# S284B.net
KiCad netlist of a schematic drawn in EAGLE
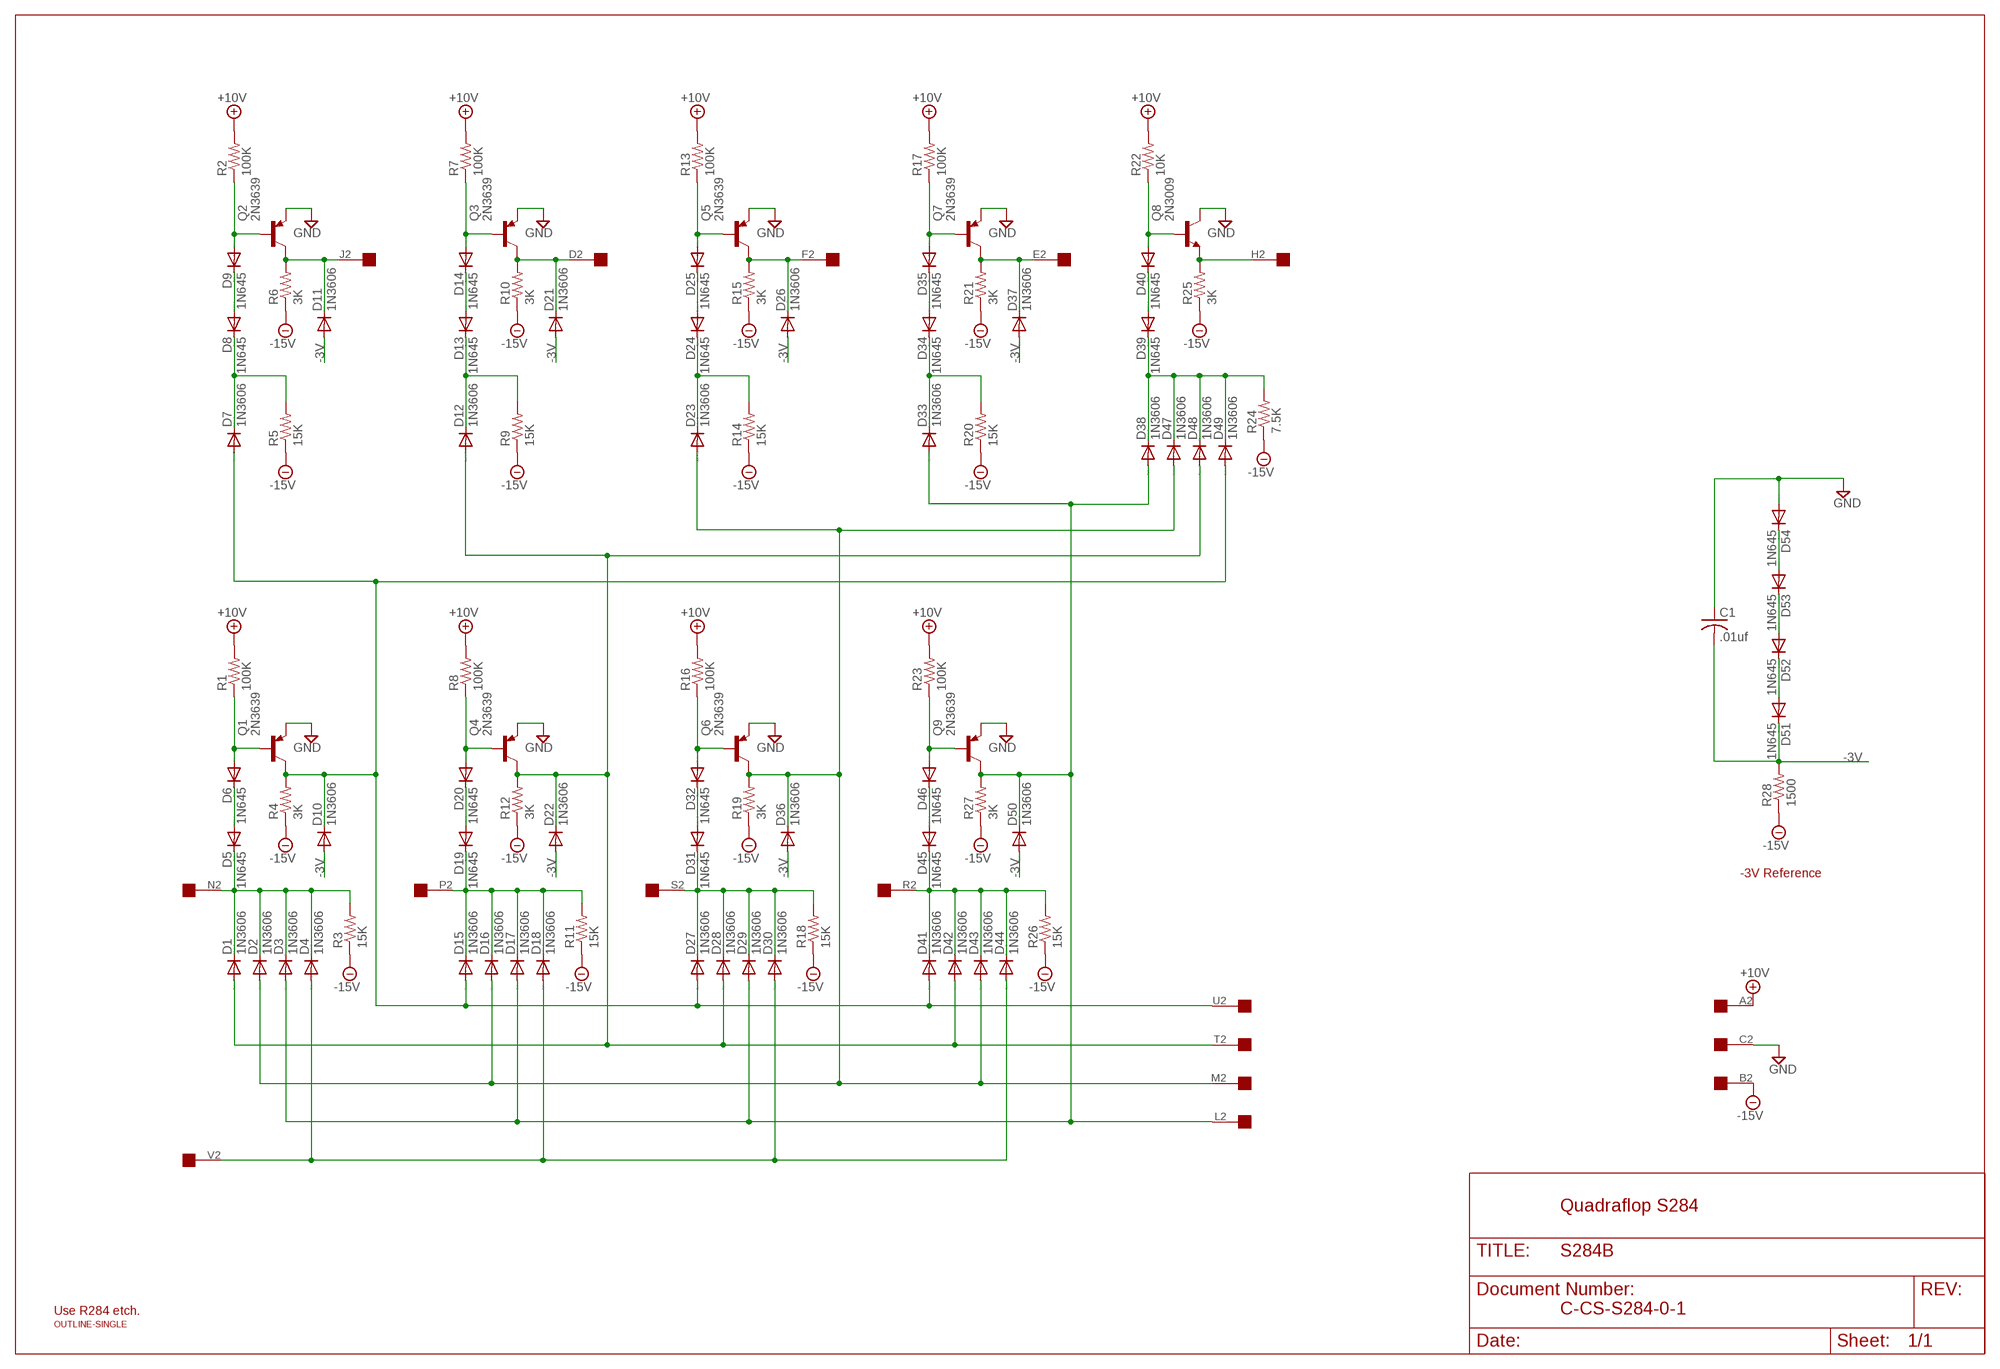
[diagram p0: schematic, sheet 1]

(export (version "E")
  (design (tool "Eeschema 10.0.6"))
  (components
    (comp (ref "C1")
      (value ".01uf")
      (footprint "eagle-import:C050-025X075")
      (libsource (lib "eagle-import") (part "C-US050-025X075"))
    )
    (comp (ref "D1")
      (value "1N3606")
      (footprint "eagle-import:DO35-10")
      (libsource (lib "eagle-import") (part "1N4148DO35-10"))
    )
    (comp (ref "D2")
      (value "1N3606")
      (footprint "eagle-import:DO35-10")
      (libsource (lib "eagle-import") (part "1N4148DO35-10"))
    )
    (comp (ref "D3")
      (value "1N3606")
      (footprint "eagle-import:DO35-10")
      (libsource (lib "eagle-import") (part "1N4148DO35-10"))
    )
    (comp (ref "D4")
      (value "1N3606")
      (footprint "eagle-import:DO35-10")
      (libsource (lib "eagle-import") (part "1N4148DO35-10"))
    )
    (comp (ref "D5")
      (value "1N645")
      (footprint "eagle-import:DO35-10")
      (libsource (lib "eagle-import") (part "1N4148DO35-10"))
    )
    (comp (ref "D6")
      (value "1N645")
      (footprint "eagle-import:DO35-10")
      (libsource (lib "eagle-import") (part "1N4148DO35-10"))
    )
    (comp (ref "D7")
      (value "1N3606")
      (footprint "eagle-import:DO35-10")
      (libsource (lib "eagle-import") (part "1N4148DO35-10"))
    )
    (comp (ref "D8")
      (value "1N645")
      (footprint "eagle-import:DO35-10")
      (libsource (lib "eagle-import") (part "1N4148DO35-10"))
    )
    (comp (ref "D9")
      (value "1N645")
      (footprint "eagle-import:DO35-10")
      (libsource (lib "eagle-import") (part "1N4148DO35-10"))
    )
    (comp (ref "D10")
      (value "1N3606")
      (footprint "eagle-import:DO35-10")
      (libsource (lib "eagle-import") (part "1N4148DO35-10"))
    )
    (comp (ref "D11")
      (value "1N3606")
      (footprint "eagle-import:DO35-10")
      (libsource (lib "eagle-import") (part "1N4148DO35-10"))
    )
    (comp (ref "D12")
      (value "1N3606")
      (footprint "eagle-import:DO35-10")
      (libsource (lib "eagle-import") (part "1N4148DO35-10"))
    )
    (comp (ref "D13")
      (value "1N645")
      (footprint "eagle-import:DO35-10")
      (libsource (lib "eagle-import") (part "1N4148DO35-10"))
    )
    (comp (ref "D14")
      (value "1N645")
      (footprint "eagle-import:DO35-10")
      (libsource (lib "eagle-import") (part "1N4148DO35-10"))
    )
    (comp (ref "D15")
      (value "1N3606")
      (footprint "eagle-import:DO35-10")
      (libsource (lib "eagle-import") (part "1N4148DO35-10"))
    )
    (comp (ref "D16")
      (value "1N3606")
      (footprint "eagle-import:DO35-10")
      (libsource (lib "eagle-import") (part "1N4148DO35-10"))
    )
    (comp (ref "D17")
      (value "1N3606")
      (footprint "eagle-import:DO35-10")
      (libsource (lib "eagle-import") (part "1N4148DO35-10"))
    )
    (comp (ref "D18")
      (value "1N3606")
      (footprint "eagle-import:DO35-10")
      (libsource (lib "eagle-import") (part "1N4148DO35-10"))
    )
    (comp (ref "D19")
      (value "1N645")
      (footprint "eagle-import:DO35-10")
      (libsource (lib "eagle-import") (part "1N4148DO35-10"))
    )
    (comp (ref "D20")
      (value "1N645")
      (footprint "eagle-import:DO35-10")
      (libsource (lib "eagle-import") (part "1N4148DO35-10"))
    )
    (comp (ref "D21")
      (value "1N3606")
      (footprint "eagle-import:DO35-10")
      (libsource (lib "eagle-import") (part "1N4148DO35-10"))
    )
    (comp (ref "D22")
      (value "1N3606")
      (footprint "eagle-import:DO35-10")
      (libsource (lib "eagle-import") (part "1N4148DO35-10"))
    )
    (comp (ref "D23")
      (value "1N3606")
      (footprint "eagle-import:DO35-10")
      (libsource (lib "eagle-import") (part "1N4148DO35-10"))
    )
    (comp (ref "D24")
      (value "1N645")
      (footprint "eagle-import:DO35-10")
      (libsource (lib "eagle-import") (part "1N4148DO35-10"))
    )
    (comp (ref "D25")
      (value "1N645")
      (footprint "eagle-import:DO35-10")
      (libsource (lib "eagle-import") (part "1N4148DO35-10"))
    )
    (comp (ref "D26")
      (value "1N3606")
      (footprint "eagle-import:DO35-10")
      (libsource (lib "eagle-import") (part "1N4148DO35-10"))
    )
    (comp (ref "D27")
      (value "1N3606")
      (footprint "eagle-import:DO35-10")
      (libsource (lib "eagle-import") (part "1N4148DO35-10"))
    )
    (comp (ref "D28")
      (value "1N3606")
      (footprint "eagle-import:DO35-10")
      (libsource (lib "eagle-import") (part "1N4148DO35-10"))
    )
    (comp (ref "D29")
      (value "1N3606")
      (footprint "eagle-import:DO35-10")
      (libsource (lib "eagle-import") (part "1N4148DO35-10"))
    )
    (comp (ref "D30")
      (value "1N3606")
      (footprint "eagle-import:DO35-10")
      (libsource (lib "eagle-import") (part "1N4148DO35-10"))
    )
    (comp (ref "D31")
      (value "1N645")
      (footprint "eagle-import:DO35-10")
      (libsource (lib "eagle-import") (part "1N4148DO35-10"))
    )
    (comp (ref "D32")
      (value "1N645")
      (footprint "eagle-import:DO35-10")
      (libsource (lib "eagle-import") (part "1N4148DO35-10"))
    )
    (comp (ref "D33")
      (value "1N3606")
      (footprint "eagle-import:DO35-10")
      (libsource (lib "eagle-import") (part "1N4148DO35-10"))
    )
    (comp (ref "D34")
      (value "1N645")
      (footprint "eagle-import:DO35-10")
      (libsource (lib "eagle-import") (part "1N4148DO35-10"))
    )
    (comp (ref "D35")
      (value "1N645")
      (footprint "eagle-import:DO35-10")
      (libsource (lib "eagle-import") (part "1N4148DO35-10"))
    )
    (comp (ref "D36")
      (value "1N3606")
      (footprint "eagle-import:DO35-10")
      (libsource (lib "eagle-import") (part "1N4148DO35-10"))
    )
    (comp (ref "D37")
      (value "1N3606")
      (footprint "eagle-import:DO35-10")
      (libsource (lib "eagle-import") (part "1N4148DO35-10"))
    )
    (comp (ref "D38")
      (value "1N3606")
      (footprint "eagle-import:DO35-10")
      (libsource (lib "eagle-import") (part "1N4148DO35-10"))
    )
    (comp (ref "D39")
      (value "1N645")
      (footprint "eagle-import:DO35-10")
      (libsource (lib "eagle-import") (part "1N4148DO35-10"))
    )
    (comp (ref "D40")
      (value "1N645")
      (footprint "eagle-import:DO35-10")
      (libsource (lib "eagle-import") (part "1N4148DO35-10"))
    )
    (comp (ref "D41")
      (value "1N3606")
      (footprint "eagle-import:DO35-10")
      (libsource (lib "eagle-import") (part "1N4148DO35-10"))
    )
    (comp (ref "D42")
      (value "1N3606")
      (footprint "eagle-import:DO35-10")
      (libsource (lib "eagle-import") (part "1N4148DO35-10"))
    )
    (comp (ref "D43")
      (value "1N3606")
      (footprint "eagle-import:DO35-10")
      (libsource (lib "eagle-import") (part "1N4148DO35-10"))
    )
    (comp (ref "D44")
      (value "1N3606")
      (footprint "eagle-import:DO35-10")
      (libsource (lib "eagle-import") (part "1N4148DO35-10"))
    )
    (comp (ref "D45")
      (value "1N645")
      (footprint "eagle-import:DO35-10")
      (libsource (lib "eagle-import") (part "1N4148DO35-10"))
    )
    (comp (ref "D46")
      (value "1N645")
      (footprint "eagle-import:DO35-10")
      (libsource (lib "eagle-import") (part "1N4148DO35-10"))
    )
    (comp (ref "D47")
      (value "1N3606")
      (footprint "eagle-import:DO35-10")
      (libsource (lib "eagle-import") (part "1N4148DO35-10"))
    )
    (comp (ref "D48")
      (value "1N3606")
      (footprint "eagle-import:DO35-10")
      (libsource (lib "eagle-import") (part "1N4148DO35-10"))
    )
    (comp (ref "D49")
      (value "1N3606")
      (footprint "eagle-import:DO35-10")
      (libsource (lib "eagle-import") (part "1N4148DO35-10"))
    )
    (comp (ref "D50")
      (value "1N3606")
      (footprint "eagle-import:DO35-10")
      (libsource (lib "eagle-import") (part "1N4148DO35-10"))
    )
    (comp (ref "D51")
      (value "1N645")
      (footprint "eagle-import:DO35-10")
      (libsource (lib "eagle-import") (part "1N4148DO35-10"))
    )
    (comp (ref "D52")
      (value "1N645")
      (footprint "eagle-import:DO35-10")
      (libsource (lib "eagle-import") (part "1N4148DO35-10"))
    )
    (comp (ref "D53")
      (value "1N645")
      (footprint "eagle-import:DO35-10")
      (libsource (lib "eagle-import") (part "1N4148DO35-10"))
    )
    (comp (ref "D54")
      (value "1N645")
      (footprint "eagle-import:DO35-10")
      (libsource (lib "eagle-import") (part "1N4148DO35-10"))
    )
    (comp (ref "Q1")
      (value "2N3639")
      (footprint "eagle-import:TO39")
      (libsource (lib "eagle-import") (part "2N3637"))
    )
    (comp (ref "Q2")
      (value "2N3639")
      (footprint "eagle-import:TO39")
      (libsource (lib "eagle-import") (part "2N3637"))
    )
    (comp (ref "Q3")
      (value "2N3639")
      (footprint "eagle-import:TO39")
      (libsource (lib "eagle-import") (part "2N3637"))
    )
    (comp (ref "Q4")
      (value "2N3639")
      (footprint "eagle-import:TO39")
      (libsource (lib "eagle-import") (part "2N3637"))
    )
    (comp (ref "Q5")
      (value "2N3639")
      (footprint "eagle-import:TO39")
      (libsource (lib "eagle-import") (part "2N3637"))
    )
    (comp (ref "Q6")
      (value "2N3639")
      (footprint "eagle-import:TO39")
      (libsource (lib "eagle-import") (part "2N3637"))
    )
    (comp (ref "Q7")
      (value "2N3639")
      (footprint "eagle-import:TO39")
      (libsource (lib "eagle-import") (part "2N3637"))
    )
    (comp (ref "Q8")
      (value "2N3009")
      (footprint "eagle-import:TO5")
      (libsource (lib "eagle-import") (part "2N2102"))
    )
    (comp (ref "Q9")
      (value "2N3639")
      (footprint "eagle-import:TO39")
      (libsource (lib "eagle-import") (part "2N3637"))
    )
    (comp (ref "R1")
      (value "100K")
      (footprint "eagle-import:0207_10")
      (libsource (lib "eagle-import") (part "R-US_0207/10"))
    )
    (comp (ref "R2")
      (value "100K")
      (footprint "eagle-import:0207_10")
      (libsource (lib "eagle-import") (part "R-US_0207/10"))
    )
    (comp (ref "R3")
      (value "15K")
      (footprint "eagle-import:0207_10")
      (libsource (lib "eagle-import") (part "R-US_0207/10"))
    )
    (comp (ref "R4")
      (value "3K")
      (footprint "eagle-import:0207_10")
      (libsource (lib "eagle-import") (part "R-US_0207/10"))
    )
    (comp (ref "R5")
      (value "15K")
      (footprint "eagle-import:0207_10")
      (libsource (lib "eagle-import") (part "R-US_0207/10"))
    )
    (comp (ref "R6")
      (value "3K")
      (footprint "eagle-import:0207_10")
      (libsource (lib "eagle-import") (part "R-US_0207/10"))
    )
    (comp (ref "R7")
      (value "100K")
      (footprint "eagle-import:0207_10")
      (libsource (lib "eagle-import") (part "R-US_0207/10"))
    )
    (comp (ref "R8")
      (value "100K")
      (footprint "eagle-import:0207_10")
      (libsource (lib "eagle-import") (part "R-US_0207/10"))
    )
    (comp (ref "R9")
      (value "15K")
      (footprint "eagle-import:0207_10")
      (libsource (lib "eagle-import") (part "R-US_0207/10"))
    )
    (comp (ref "R10")
      (value "3K")
      (footprint "eagle-import:0207_10")
      (libsource (lib "eagle-import") (part "R-US_0207/10"))
    )
    (comp (ref "R11")
      (value "15K")
      (footprint "eagle-import:0207_10")
      (libsource (lib "eagle-import") (part "R-US_0207/10"))
    )
    (comp (ref "R12")
      (value "3K")
      (footprint "eagle-import:0207_10")
      (libsource (lib "eagle-import") (part "R-US_0207/10"))
    )
    (comp (ref "R13")
      (value "100K")
      (footprint "eagle-import:0207_10")
      (libsource (lib "eagle-import") (part "R-US_0207/10"))
    )
    (comp (ref "R14")
      (value "15K")
      (footprint "eagle-import:0207_10")
      (libsource (lib "eagle-import") (part "R-US_0207/10"))
    )
    (comp (ref "R15")
      (value "3K")
      (footprint "eagle-import:0207_10")
      (libsource (lib "eagle-import") (part "R-US_0207/10"))
    )
    (comp (ref "R16")
      (value "100K")
      (footprint "eagle-import:0207_10")
      (libsource (lib "eagle-import") (part "R-US_0207/10"))
    )
    (comp (ref "R17")
      (value "100K")
      (footprint "eagle-import:0207_10")
      (libsource (lib "eagle-import") (part "R-US_0207/10"))
    )
    (comp (ref "R18")
      (value "15K")
      (footprint "eagle-import:0207_10")
      (libsource (lib "eagle-import") (part "R-US_0207/10"))
    )
    (comp (ref "R19")
      (value "3K")
      (footprint "eagle-import:0207_10")
      (libsource (lib "eagle-import") (part "R-US_0207/10"))
    )
    (comp (ref "R20")
      (value "15K")
      (footprint "eagle-import:0207_10")
      (libsource (lib "eagle-import") (part "R-US_0207/10"))
    )
    (comp (ref "R21")
      (value "3K")
      (footprint "eagle-import:0207_10")
      (libsource (lib "eagle-import") (part "R-US_0207/10"))
    )
    (comp (ref "R22")
      (value "10K")
      (footprint "eagle-import:0207_10")
      (libsource (lib "eagle-import") (part "R-US_0207/10"))
    )
    (comp (ref "R23")
      (value "100K")
      (footprint "eagle-import:0207_10")
      (libsource (lib "eagle-import") (part "R-US_0207/10"))
    )
    (comp (ref "R24")
      (value "7.5K")
      (footprint "eagle-import:0207_10")
      (libsource (lib "eagle-import") (part "R-US_0207/10"))
    )
    (comp (ref "R25")
      (value "3K")
      (footprint "eagle-import:0207_10")
      (libsource (lib "eagle-import") (part "R-US_0207/10"))
    )
    (comp (ref "R26")
      (value "15K")
      (footprint "eagle-import:0207_10")
      (libsource (lib "eagle-import") (part "R-US_0207/10"))
    )
    (comp (ref "R27")
      (value "3K")
      (footprint "eagle-import:0207_10")
      (libsource (lib "eagle-import") (part "R-US_0207/10"))
    )
    (comp (ref "R28")
      (value "1500")
      (footprint "eagle-import:0207_10")
      (libsource (lib "eagle-import") (part "R-US_0207/10"))
    )
    (comp (ref "U$1")
      (value "OUTLINE-SINGLE")
      (footprint "eagle-import:SINGLE")
      (libsource (lib "eagle-import") (part "OUTLINE-SINGLE"))
    )
    (comp (ref "U$2")
      (value "EDGE-1")
      (footprint "eagle-import:EDGE-CON1")
      (libsource (lib "eagle-import") (part "EDGE-1"))
    )
  )
  (nets
    (net (code "1") (name "+10V") (class "Default")
      (node (ref "R1") (pin "2") (pinfunction "2_2") (pintype "passive"))
      (node (ref "R13") (pin "2") (pinfunction "2_2") (pintype "passive"))
      (node (ref "R16") (pin "2") (pinfunction "2_2") (pintype "passive"))
      (node (ref "R17") (pin "2") (pinfunction "2_2") (pintype "passive"))
      (node (ref "R2") (pin "2") (pinfunction "2_2") (pintype "passive"))
      (node (ref "R22") (pin "2") (pinfunction "2_2") (pintype "passive"))
      (node (ref "R23") (pin "2") (pinfunction "2_2") (pintype "passive"))
      (node (ref "R7") (pin "2") (pinfunction "2_2") (pintype "passive"))
      (node (ref "R8") (pin "2") (pinfunction "2_2") (pintype "passive"))
      (node (ref "U$2") (pin "A2") (pinfunction "1_A2") (pintype "bidirectional"))
    )
    (net (code "2") (name "-15V") (class "Default")
      (node (ref "R10") (pin "1") (pinfunction "1_1") (pintype "passive"))
      (node (ref "R11") (pin "1") (pinfunction "1_1") (pintype "passive"))
      (node (ref "R12") (pin "1") (pinfunction "1_1") (pintype "passive"))
      (node (ref "R14") (pin "1") (pinfunction "1_1") (pintype "passive"))
      (node (ref "R15") (pin "1") (pinfunction "1_1") (pintype "passive"))
      (node (ref "R18") (pin "1") (pinfunction "1_1") (pintype "passive"))
      (node (ref "R19") (pin "1") (pinfunction "1_1") (pintype "passive"))
      (node (ref "R20") (pin "1") (pinfunction "1_1") (pintype "passive"))
      (node (ref "R21") (pin "1") (pinfunction "1_1") (pintype "passive"))
      (node (ref "R24") (pin "1") (pinfunction "1_1") (pintype "passive"))
      (node (ref "R25") (pin "1") (pinfunction "1_1") (pintype "passive"))
      (node (ref "R26") (pin "1") (pinfunction "1_1") (pintype "passive"))
      (node (ref "R27") (pin "1") (pinfunction "1_1") (pintype "passive"))
      (node (ref "R28") (pin "1") (pinfunction "1_1") (pintype "passive"))
      (node (ref "R3") (pin "1") (pinfunction "1_1") (pintype "passive"))
      (node (ref "R4") (pin "1") (pinfunction "1_1") (pintype "passive"))
      (node (ref "R5") (pin "1") (pinfunction "1_1") (pintype "passive"))
      (node (ref "R6") (pin "1") (pinfunction "1_1") (pintype "passive"))
      (node (ref "R9") (pin "1") (pinfunction "1_1") (pintype "passive"))
      (node (ref "U$2") (pin "B2") (pinfunction "1_B2") (pintype "bidirectional"))
    )
    (net (code "3") (name "/-3V") (class "Default")
      (node (ref "C1") (pin "2") (pinfunction "2_2") (pintype "passive"))
      (node (ref "D10") (pin "A") (pinfunction "A_A") (pintype "passive"))
      (node (ref "D11") (pin "A") (pinfunction "A_A") (pintype "passive"))
      (node (ref "D21") (pin "A") (pinfunction "A_A") (pintype "passive"))
      (node (ref "D22") (pin "A") (pinfunction "A_A") (pintype "passive"))
      (node (ref "D26") (pin "A") (pinfunction "A_A") (pintype "passive"))
      (node (ref "D36") (pin "A") (pinfunction "A_A") (pintype "passive"))
      (node (ref "D37") (pin "A") (pinfunction "A_A") (pintype "passive"))
      (node (ref "D50") (pin "A") (pinfunction "A_A") (pintype "passive"))
      (node (ref "D51") (pin "C") (pinfunction "C_C") (pintype "passive"))
      (node (ref "R28") (pin "2") (pinfunction "2_2") (pintype "passive"))
    )
    (net (code "4") (name "GND") (class "Default")
      (node (ref "C1") (pin "1") (pinfunction "1_1") (pintype "passive"))
      (node (ref "D54") (pin "A") (pinfunction "A_A") (pintype "passive"))
      (node (ref "Q1") (pin "1") (pinfunction "E_1") (pintype "passive"))
      (node (ref "Q2") (pin "1") (pinfunction "E_1") (pintype "passive"))
      (node (ref "Q3") (pin "1") (pinfunction "E_1") (pintype "passive"))
      (node (ref "Q4") (pin "1") (pinfunction "E_1") (pintype "passive"))
      (node (ref "Q5") (pin "1") (pinfunction "E_1") (pintype "passive"))
      (node (ref "Q6") (pin "1") (pinfunction "E_1") (pintype "passive"))
      (node (ref "Q7") (pin "1") (pinfunction "E_1") (pintype "passive"))
      (node (ref "Q8") (pin "3") (pinfunction "C_3") (pintype "passive"))
      (node (ref "Q9") (pin "1") (pinfunction "E_1") (pintype "passive"))
      (node (ref "U$2") (pin "C2") (pinfunction "1_C2") (pintype "bidirectional"))
    )
    (net (code "5") (name "Net-(D5-PadA)") (class "Default")
      (node (ref "D5") (pin "A") (pinfunction "A_A") (pintype "passive"))
      (node (ref "D6") (pin "C") (pinfunction "C_C") (pintype "passive"))
    )
    (net (code "6") (name "Net-(D7-PadC)") (class "Default")
      (node (ref "D7") (pin "C") (pinfunction "C_C") (pintype "passive"))
      (node (ref "D8") (pin "C") (pinfunction "C_C") (pintype "passive"))
      (node (ref "R5") (pin "2") (pinfunction "2_2") (pintype "passive"))
    )
    (net (code "7") (name "Net-(D8-PadA)") (class "Default")
      (node (ref "D8") (pin "A") (pinfunction "A_A") (pintype "passive"))
      (node (ref "D9") (pin "C") (pinfunction "C_C") (pintype "passive"))
    )
    (net (code "8") (name "Net-(D12-PadC)") (class "Default")
      (node (ref "D12") (pin "C") (pinfunction "C_C") (pintype "passive"))
      (node (ref "D13") (pin "C") (pinfunction "C_C") (pintype "passive"))
      (node (ref "R9") (pin "2") (pinfunction "2_2") (pintype "passive"))
    )
    (net (code "9") (name "Net-(D13-PadA)") (class "Default")
      (node (ref "D13") (pin "A") (pinfunction "A_A") (pintype "passive"))
      (node (ref "D14") (pin "C") (pinfunction "C_C") (pintype "passive"))
    )
    (net (code "10") (name "Net-(D19-PadA)") (class "Default")
      (node (ref "D19") (pin "A") (pinfunction "A_A") (pintype "passive"))
      (node (ref "D20") (pin "C") (pinfunction "C_C") (pintype "passive"))
    )
    (net (code "11") (name "Net-(D23-PadC)") (class "Default")
      (node (ref "D23") (pin "C") (pinfunction "C_C") (pintype "passive"))
      (node (ref "D24") (pin "C") (pinfunction "C_C") (pintype "passive"))
      (node (ref "R14") (pin "2") (pinfunction "2_2") (pintype "passive"))
    )
    (net (code "12") (name "Net-(D24-PadA)") (class "Default")
      (node (ref "D24") (pin "A") (pinfunction "A_A") (pintype "passive"))
      (node (ref "D25") (pin "C") (pinfunction "C_C") (pintype "passive"))
    )
    (net (code "13") (name "Net-(D31-PadA)") (class "Default")
      (node (ref "D31") (pin "A") (pinfunction "A_A") (pintype "passive"))
      (node (ref "D32") (pin "C") (pinfunction "C_C") (pintype "passive"))
    )
    (net (code "14") (name "Net-(D33-PadC)") (class "Default")
      (node (ref "D33") (pin "C") (pinfunction "C_C") (pintype "passive"))
      (node (ref "D34") (pin "C") (pinfunction "C_C") (pintype "passive"))
      (node (ref "R20") (pin "2") (pinfunction "2_2") (pintype "passive"))
    )
    (net (code "15") (name "Net-(D34-PadA)") (class "Default")
      (node (ref "D34") (pin "A") (pinfunction "A_A") (pintype "passive"))
      (node (ref "D35") (pin "C") (pinfunction "C_C") (pintype "passive"))
    )
    (net (code "16") (name "Net-(D38-PadC)") (class "Default")
      (node (ref "D38") (pin "C") (pinfunction "C_C") (pintype "passive"))
      (node (ref "D39") (pin "C") (pinfunction "C_C") (pintype "passive"))
      (node (ref "D47") (pin "C") (pinfunction "C_C") (pintype "passive"))
      (node (ref "D48") (pin "C") (pinfunction "C_C") (pintype "passive"))
      (node (ref "D49") (pin "C") (pinfunction "C_C") (pintype "passive"))
      (node (ref "R24") (pin "2") (pinfunction "2_2") (pintype "passive"))
    )
    (net (code "17") (name "Net-(D39-PadA)") (class "Default")
      (node (ref "D39") (pin "A") (pinfunction "A_A") (pintype "passive"))
      (node (ref "D40") (pin "C") (pinfunction "C_C") (pintype "passive"))
    )
    (net (code "18") (name "Net-(D45-PadA)") (class "Default")
      (node (ref "D45") (pin "A") (pinfunction "A_A") (pintype "passive"))
      (node (ref "D46") (pin "C") (pinfunction "C_C") (pintype "passive"))
    )
    (net (code "19") (name "Net-(D51-PadA)") (class "Default")
      (node (ref "D51") (pin "A") (pinfunction "A_A") (pintype "passive"))
      (node (ref "D52") (pin "C") (pinfunction "C_C") (pintype "passive"))
    )
    (net (code "20") (name "Net-(D52-PadA)") (class "Default")
      (node (ref "D52") (pin "A") (pinfunction "A_A") (pintype "passive"))
      (node (ref "D53") (pin "C") (pinfunction "C_C") (pintype "passive"))
    )
    (net (code "21") (name "Net-(D53-PadA)") (class "Default")
      (node (ref "D53") (pin "A") (pinfunction "A_A") (pintype "passive"))
      (node (ref "D54") (pin "C") (pinfunction "C_C") (pintype "passive"))
    )
    (net (code "22") (name "Net-(Q1-B)") (class "Default")
      (node (ref "D6") (pin "A") (pinfunction "A_A") (pintype "passive"))
      (node (ref "Q1") (pin "2") (pinfunction "B_2") (pintype "passive"))
      (node (ref "R1") (pin "1") (pinfunction "1_1") (pintype "passive"))
    )
    (net (code "23") (name "Net-(Q1-C)") (class "Default")
      (node (ref "D10") (pin "C") (pinfunction "C_C") (pintype "passive"))
      (node (ref "D15") (pin "A") (pinfunction "A_A") (pintype "passive"))
      (node (ref "D27") (pin "A") (pinfunction "A_A") (pintype "passive"))
      (node (ref "D41") (pin "A") (pinfunction "A_A") (pintype "passive"))
      (node (ref "D49") (pin "A") (pinfunction "A_A") (pintype "passive"))
      (node (ref "D7") (pin "A") (pinfunction "A_A") (pintype "passive"))
      (node (ref "Q1") (pin "3") (pinfunction "C_3") (pintype "passive"))
      (node (ref "R4") (pin "2") (pinfunction "2_2") (pintype "passive"))
      (node (ref "U$2") (pin "U2") (pinfunction "1_U2") (pintype "bidirectional"))
    )
    (net (code "24") (name "Net-(Q2-B)") (class "Default")
      (node (ref "D9") (pin "A") (pinfunction "A_A") (pintype "passive"))
      (node (ref "Q2") (pin "2") (pinfunction "B_2") (pintype "passive"))
      (node (ref "R2") (pin "1") (pinfunction "1_1") (pintype "passive"))
    )
    (net (code "25") (name "Net-(Q2-C)") (class "Default")
      (node (ref "D11") (pin "C") (pinfunction "C_C") (pintype "passive"))
      (node (ref "Q2") (pin "3") (pinfunction "C_3") (pintype "passive"))
      (node (ref "R6") (pin "2") (pinfunction "2_2") (pintype "passive"))
      (node (ref "U$2") (pin "J2") (pinfunction "1_J2") (pintype "bidirectional"))
    )
    (net (code "26") (name "Net-(Q3-B)") (class "Default")
      (node (ref "D14") (pin "A") (pinfunction "A_A") (pintype "passive"))
      (node (ref "Q3") (pin "2") (pinfunction "B_2") (pintype "passive"))
      (node (ref "R7") (pin "1") (pinfunction "1_1") (pintype "passive"))
    )
    (net (code "27") (name "Net-(Q3-C)") (class "Default")
      (node (ref "D21") (pin "C") (pinfunction "C_C") (pintype "passive"))
      (node (ref "Q3") (pin "3") (pinfunction "C_3") (pintype "passive"))
      (node (ref "R10") (pin "2") (pinfunction "2_2") (pintype "passive"))
      (node (ref "U$2") (pin "D2") (pinfunction "1_D2") (pintype "bidirectional"))
    )
    (net (code "28") (name "Net-(Q4-B)") (class "Default")
      (node (ref "D20") (pin "A") (pinfunction "A_A") (pintype "passive"))
      (node (ref "Q4") (pin "2") (pinfunction "B_2") (pintype "passive"))
      (node (ref "R8") (pin "1") (pinfunction "1_1") (pintype "passive"))
    )
    (net (code "29") (name "Net-(Q4-C)") (class "Default")
      (node (ref "D1") (pin "A") (pinfunction "A_A") (pintype "passive"))
      (node (ref "D12") (pin "A") (pinfunction "A_A") (pintype "passive"))
      (node (ref "D22") (pin "C") (pinfunction "C_C") (pintype "passive"))
      (node (ref "D28") (pin "A") (pinfunction "A_A") (pintype "passive"))
      (node (ref "D42") (pin "A") (pinfunction "A_A") (pintype "passive"))
      (node (ref "D48") (pin "A") (pinfunction "A_A") (pintype "passive"))
      (node (ref "Q4") (pin "3") (pinfunction "C_3") (pintype "passive"))
      (node (ref "R12") (pin "2") (pinfunction "2_2") (pintype "passive"))
      (node (ref "U$2") (pin "T2") (pinfunction "1_T2") (pintype "bidirectional"))
    )
    (net (code "30") (name "Net-(Q5-B)") (class "Default")
      (node (ref "D25") (pin "A") (pinfunction "A_A") (pintype "passive"))
      (node (ref "Q5") (pin "2") (pinfunction "B_2") (pintype "passive"))
      (node (ref "R13") (pin "1") (pinfunction "1_1") (pintype "passive"))
    )
    (net (code "31") (name "Net-(Q5-C)") (class "Default")
      (node (ref "D26") (pin "C") (pinfunction "C_C") (pintype "passive"))
      (node (ref "Q5") (pin "3") (pinfunction "C_3") (pintype "passive"))
      (node (ref "R15") (pin "2") (pinfunction "2_2") (pintype "passive"))
      (node (ref "U$2") (pin "F2") (pinfunction "1_F2") (pintype "bidirectional"))
    )
    (net (code "32") (name "Net-(Q6-B)") (class "Default")
      (node (ref "D32") (pin "A") (pinfunction "A_A") (pintype "passive"))
      (node (ref "Q6") (pin "2") (pinfunction "B_2") (pintype "passive"))
      (node (ref "R16") (pin "1") (pinfunction "1_1") (pintype "passive"))
    )
    (net (code "33") (name "Net-(Q6-C)") (class "Default")
      (node (ref "D16") (pin "A") (pinfunction "A_A") (pintype "passive"))
      (node (ref "D2") (pin "A") (pinfunction "A_A") (pintype "passive"))
      (node (ref "D23") (pin "A") (pinfunction "A_A") (pintype "passive"))
      (node (ref "D36") (pin "C") (pinfunction "C_C") (pintype "passive"))
      (node (ref "D43") (pin "A") (pinfunction "A_A") (pintype "passive"))
      (node (ref "D47") (pin "A") (pinfunction "A_A") (pintype "passive"))
      (node (ref "Q6") (pin "3") (pinfunction "C_3") (pintype "passive"))
      (node (ref "R19") (pin "2") (pinfunction "2_2") (pintype "passive"))
      (node (ref "U$2") (pin "M2") (pinfunction "1_M2") (pintype "bidirectional"))
    )
    (net (code "34") (name "Net-(Q7-B)") (class "Default")
      (node (ref "D35") (pin "A") (pinfunction "A_A") (pintype "passive"))
      (node (ref "Q7") (pin "2") (pinfunction "B_2") (pintype "passive"))
      (node (ref "R17") (pin "1") (pinfunction "1_1") (pintype "passive"))
    )
    (net (code "35") (name "Net-(Q7-C)") (class "Default")
      (node (ref "D37") (pin "C") (pinfunction "C_C") (pintype "passive"))
      (node (ref "Q7") (pin "3") (pinfunction "C_3") (pintype "passive"))
      (node (ref "R21") (pin "2") (pinfunction "2_2") (pintype "passive"))
      (node (ref "U$2") (pin "E2") (pinfunction "1_E2") (pintype "bidirectional"))
    )
    (net (code "36") (name "Net-(Q8-B)") (class "Default")
      (node (ref "D40") (pin "A") (pinfunction "A_A") (pintype "passive"))
      (node (ref "Q8") (pin "2") (pinfunction "B_2") (pintype "passive"))
      (node (ref "R22") (pin "1") (pinfunction "1_1") (pintype "passive"))
    )
    (net (code "37") (name "Net-(Q8-E)") (class "Default")
      (node (ref "Q8") (pin "1") (pinfunction "E_1") (pintype "passive"))
      (node (ref "R25") (pin "2") (pinfunction "2_2") (pintype "passive"))
      (node (ref "U$2") (pin "H2") (pinfunction "1_H2") (pintype "bidirectional"))
    )
    (net (code "38") (name "Net-(Q9-B)") (class "Default")
      (node (ref "D46") (pin "A") (pinfunction "A_A") (pintype "passive"))
      (node (ref "Q9") (pin "2") (pinfunction "B_2") (pintype "passive"))
      (node (ref "R23") (pin "1") (pinfunction "1_1") (pintype "passive"))
    )
    (net (code "39") (name "Net-(Q9-C)") (class "Default")
      (node (ref "D17") (pin "A") (pinfunction "A_A") (pintype "passive"))
      (node (ref "D29") (pin "A") (pinfunction "A_A") (pintype "passive"))
      (node (ref "D3") (pin "A") (pinfunction "A_A") (pintype "passive"))
      (node (ref "D33") (pin "A") (pinfunction "A_A") (pintype "passive"))
      (node (ref "D38") (pin "A") (pinfunction "A_A") (pintype "passive"))
      (node (ref "D50") (pin "C") (pinfunction "C_C") (pintype "passive"))
      (node (ref "Q9") (pin "3") (pinfunction "C_3") (pintype "passive"))
      (node (ref "R27") (pin "2") (pinfunction "2_2") (pintype "passive"))
      (node (ref "U$2") (pin "L2") (pinfunction "1_L2") (pintype "bidirectional"))
    )
    (net (code "40") (name "Net-(U$2L-1)") (class "Default")
      (node (ref "D1") (pin "C") (pinfunction "C_C") (pintype "passive"))
      (node (ref "D2") (pin "C") (pinfunction "C_C") (pintype "passive"))
      (node (ref "D3") (pin "C") (pinfunction "C_C") (pintype "passive"))
      (node (ref "D4") (pin "C") (pinfunction "C_C") (pintype "passive"))
      (node (ref "D5") (pin "C") (pinfunction "C_C") (pintype "passive"))
      (node (ref "R3") (pin "2") (pinfunction "2_2") (pintype "passive"))
      (node (ref "U$2") (pin "N2") (pinfunction "1_N2") (pintype "bidirectional"))
    )
    (net (code "41") (name "Net-(U$2M-1)") (class "Default")
      (node (ref "D15") (pin "C") (pinfunction "C_C") (pintype "passive"))
      (node (ref "D16") (pin "C") (pinfunction "C_C") (pintype "passive"))
      (node (ref "D17") (pin "C") (pinfunction "C_C") (pintype "passive"))
      (node (ref "D18") (pin "C") (pinfunction "C_C") (pintype "passive"))
      (node (ref "D19") (pin "C") (pinfunction "C_C") (pintype "passive"))
      (node (ref "R11") (pin "2") (pinfunction "2_2") (pintype "passive"))
      (node (ref "U$2") (pin "P2") (pinfunction "1_P2") (pintype "bidirectional"))
    )
    (net (code "42") (name "Net-(U$2N-1)") (class "Default")
      (node (ref "D41") (pin "C") (pinfunction "C_C") (pintype "passive"))
      (node (ref "D42") (pin "C") (pinfunction "C_C") (pintype "passive"))
      (node (ref "D43") (pin "C") (pinfunction "C_C") (pintype "passive"))
      (node (ref "D44") (pin "C") (pinfunction "C_C") (pintype "passive"))
      (node (ref "D45") (pin "C") (pinfunction "C_C") (pintype "passive"))
      (node (ref "R26") (pin "2") (pinfunction "2_2") (pintype "passive"))
      (node (ref "U$2") (pin "R2") (pinfunction "1_R2") (pintype "bidirectional"))
    )
    (net (code "43") (name "Net-(U$2O-1)") (class "Default")
      (node (ref "D27") (pin "C") (pinfunction "C_C") (pintype "passive"))
      (node (ref "D28") (pin "C") (pinfunction "C_C") (pintype "passive"))
      (node (ref "D29") (pin "C") (pinfunction "C_C") (pintype "passive"))
      (node (ref "D30") (pin "C") (pinfunction "C_C") (pintype "passive"))
      (node (ref "D31") (pin "C") (pinfunction "C_C") (pintype "passive"))
      (node (ref "R18") (pin "2") (pinfunction "2_2") (pintype "passive"))
      (node (ref "U$2") (pin "S2") (pinfunction "1_S2") (pintype "bidirectional"))
    )
    (net (code "44") (name "Net-(U$2R-1)") (class "Default")
      (node (ref "D18") (pin "A") (pinfunction "A_A") (pintype "passive"))
      (node (ref "D30") (pin "A") (pinfunction "A_A") (pintype "passive"))
      (node (ref "D4") (pin "A") (pinfunction "A_A") (pintype "passive"))
      (node (ref "D44") (pin "A") (pinfunction "A_A") (pintype "passive"))
      (node (ref "U$2") (pin "V2") (pinfunction "1_V2") (pintype "bidirectional"))
    )
  )
)
